# Mounting_PCB_LED.net
KiCad netlist of a schematic drawn in Altium Designer
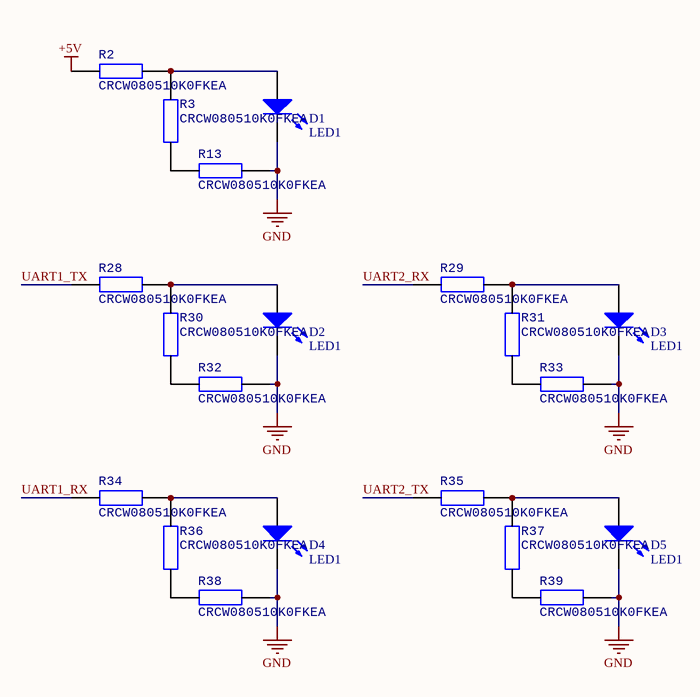
[diagram p0: Mounting_PCB_LED.SchDoc]

(export (version "E")
  (design (tool "Eeschema 10.0.6"))
  (components
    (comp (ref "D1")
      (value "LED1")
      (footprint "L0603")
      (description "Typical RED GaAs LED")
      (fields (field (name "PUBLISHER") "Altium Limited"))
      (libsource (lib "Miscellaneous Devices") (part "LED1"))
    )
    (comp (ref "D2")
      (value "LED1")
      (footprint "L0603")
      (description "Typical RED GaAs LED")
      (fields (field (name "PUBLISHER") "Altium Limited"))
      (libsource (lib "Miscellaneous Devices") (part "LED1"))
    )
    (comp (ref "D3")
      (value "LED1")
      (footprint "L0603")
      (description "Typical RED GaAs LED")
      (fields (field (name "PUBLISHER") "Altium Limited"))
      (libsource (lib "Miscellaneous Devices") (part "LED1"))
    )
    (comp (ref "D4")
      (value "LED1")
      (footprint "L0603")
      (description "Typical RED GaAs LED")
      (fields (field (name "PUBLISHER") "Altium Limited"))
      (libsource (lib "Miscellaneous Devices") (part "LED1"))
    )
    (comp (ref "D5")
      (value "LED1")
      (footprint "L0603")
      (description "Typical RED GaAs LED")
      (fields (field (name "PUBLISHER") "Altium Limited"))
      (libsource (lib "Miscellaneous Devices") (part "LED1"))
    )
    (comp (ref "R2")
      (value "CRCW080510K0FKEA")
      (footprint "RESC2012X50N")
      (fields (field (name "RS PART NUMBER") "1694499"))
      (libsource (lib "CRCW080510K0FKEA") (part "CRCW080510K0FKEA"))
    )
    (comp (ref "R3")
      (value "CRCW080510K0FKEA")
      (footprint "RESC2012X50N")
      (fields (field (name "RS PART NUMBER") "1694499"))
      (libsource (lib "CRCW080510K0FKEA") (part "CRCW080510K0FKEA"))
    )
    (comp (ref "R13")
      (value "CRCW080510K0FKEA")
      (footprint "RESC2012X50N")
      (fields (field (name "RS PART NUMBER") "1694499"))
      (libsource (lib "CRCW080510K0FKEA") (part "CRCW080510K0FKEA"))
    )
    (comp (ref "R28")
      (value "CRCW080510K0FKEA")
      (footprint "RESC2012X50N")
      (fields (field (name "RS PART NUMBER") "1694499"))
      (libsource (lib "CRCW080510K0FKEA") (part "CRCW080510K0FKEA"))
    )
    (comp (ref "R29")
      (value "CRCW080510K0FKEA")
      (footprint "RESC2012X50N")
      (fields (field (name "RS PART NUMBER") "1694499"))
      (libsource (lib "CRCW080510K0FKEA") (part "CRCW080510K0FKEA"))
    )
    (comp (ref "R30")
      (value "CRCW080510K0FKEA")
      (footprint "RESC2012X50N")
      (fields (field (name "RS PART NUMBER") "1694499"))
      (libsource (lib "CRCW080510K0FKEA") (part "CRCW080510K0FKEA"))
    )
    (comp (ref "R31")
      (value "CRCW080510K0FKEA")
      (footprint "RESC2012X50N")
      (fields (field (name "RS PART NUMBER") "1694499"))
      (libsource (lib "CRCW080510K0FKEA") (part "CRCW080510K0FKEA"))
    )
    (comp (ref "R32")
      (value "CRCW080510K0FKEA")
      (footprint "RESC2012X50N")
      (fields (field (name "RS PART NUMBER") "1694499"))
      (libsource (lib "CRCW080510K0FKEA") (part "CRCW080510K0FKEA"))
    )
    (comp (ref "R33")
      (value "CRCW080510K0FKEA")
      (footprint "RESC2012X50N")
      (fields (field (name "RS PART NUMBER") "1694499"))
      (libsource (lib "CRCW080510K0FKEA") (part "CRCW080510K0FKEA"))
    )
    (comp (ref "R34")
      (value "CRCW080510K0FKEA")
      (footprint "RESC2012X50N")
      (fields (field (name "RS PART NUMBER") "1694499"))
      (libsource (lib "CRCW080510K0FKEA") (part "CRCW080510K0FKEA"))
    )
    (comp (ref "R35")
      (value "CRCW080510K0FKEA")
      (footprint "RESC2012X50N")
      (fields (field (name "RS PART NUMBER") "1694499"))
      (libsource (lib "CRCW080510K0FKEA") (part "CRCW080510K0FKEA"))
    )
    (comp (ref "R36")
      (value "CRCW080510K0FKEA")
      (footprint "RESC2012X50N")
      (fields (field (name "RS PART NUMBER") "1694499"))
      (libsource (lib "CRCW080510K0FKEA") (part "CRCW080510K0FKEA"))
    )
    (comp (ref "R37")
      (value "CRCW080510K0FKEA")
      (footprint "RESC2012X50N")
      (fields (field (name "RS PART NUMBER") "1694499"))
      (libsource (lib "CRCW080510K0FKEA") (part "CRCW080510K0FKEA"))
    )
    (comp (ref "R38")
      (value "CRCW080510K0FKEA")
      (footprint "RESC2012X50N")
      (fields (field (name "RS PART NUMBER") "1694499"))
      (libsource (lib "CRCW080510K0FKEA") (part "CRCW080510K0FKEA"))
    )
    (comp (ref "R39")
      (value "CRCW080510K0FKEA")
      (footprint "RESC2012X50N")
      (fields (field (name "RS PART NUMBER") "1694499"))
      (libsource (lib "CRCW080510K0FKEA") (part "CRCW080510K0FKEA"))
    )
  )
  (nets
    (net (code "1") (name "+5V") (class "Default")
      (node (ref "R2") (pin "1") (pinfunction "1_1") (pintype "passive"))
    )
    (net (code "2") (name "/UART1_RX") (class "Default")
      (node (ref "R34") (pin "1") (pinfunction "1_1") (pintype "passive"))
    )
    (net (code "3") (name "/UART1_TX") (class "Default")
      (node (ref "R28") (pin "1") (pinfunction "1_1") (pintype "passive"))
    )
    (net (code "4") (name "/UART2_RX") (class "Default")
      (node (ref "R29") (pin "1") (pinfunction "1_1") (pintype "passive"))
    )
    (net (code "5") (name "/UART2_TX") (class "Default")
      (node (ref "R35") (pin "1") (pinfunction "1_1") (pintype "passive"))
    )
    (net (code "6") (name "GND") (class "Default")
      (node (ref "D1") (pin "2") (pinfunction "K_2") (pintype "passive"))
      (node (ref "D2") (pin "2") (pinfunction "K_2") (pintype "passive"))
      (node (ref "D3") (pin "2") (pinfunction "K_2") (pintype "passive"))
      (node (ref "D4") (pin "2") (pinfunction "K_2") (pintype "passive"))
      (node (ref "D5") (pin "2") (pinfunction "K_2") (pintype "passive"))
      (node (ref "R13") (pin "1") (pinfunction "1_1") (pintype "passive"))
      (node (ref "R32") (pin "1") (pinfunction "1_1") (pintype "passive"))
      (node (ref "R33") (pin "1") (pinfunction "1_1") (pintype "passive"))
      (node (ref "R38") (pin "1") (pinfunction "1_1") (pintype "passive"))
      (node (ref "R39") (pin "1") (pinfunction "1_1") (pintype "passive"))
    )
    (net (code "7") (name "Net-(D1-A)") (class "Default")
      (node (ref "D1") (pin "1") (pinfunction "A_1") (pintype "passive"))
      (node (ref "R2") (pin "2") (pinfunction "2_2") (pintype "passive"))
      (node (ref "R3") (pin "2") (pinfunction "2_2") (pintype "passive"))
    )
    (net (code "8") (name "Net-(D2-A)") (class "Default")
      (node (ref "D2") (pin "1") (pinfunction "A_1") (pintype "passive"))
      (node (ref "R28") (pin "2") (pinfunction "2_2") (pintype "passive"))
      (node (ref "R30") (pin "2") (pinfunction "2_2") (pintype "passive"))
    )
    (net (code "9") (name "Net-(D3-A)") (class "Default")
      (node (ref "D3") (pin "1") (pinfunction "A_1") (pintype "passive"))
      (node (ref "R29") (pin "2") (pinfunction "2_2") (pintype "passive"))
      (node (ref "R31") (pin "2") (pinfunction "2_2") (pintype "passive"))
    )
    (net (code "10") (name "Net-(D4-A)") (class "Default")
      (node (ref "D4") (pin "1") (pinfunction "A_1") (pintype "passive"))
      (node (ref "R34") (pin "2") (pinfunction "2_2") (pintype "passive"))
      (node (ref "R36") (pin "2") (pinfunction "2_2") (pintype "passive"))
    )
    (net (code "11") (name "Net-(D5-A)") (class "Default")
      (node (ref "D5") (pin "1") (pinfunction "A_1") (pintype "passive"))
      (node (ref "R35") (pin "2") (pinfunction "2_2") (pintype "passive"))
      (node (ref "R37") (pin "2") (pinfunction "2_2") (pintype "passive"))
    )
    (net (code "12") (name "Net-(R13-Pad2)") (class "Default")
      (node (ref "R13") (pin "2") (pinfunction "2_2") (pintype "passive"))
      (node (ref "R3") (pin "1") (pinfunction "1_1") (pintype "passive"))
    )
    (net (code "13") (name "Net-(R30-Pad1)") (class "Default")
      (node (ref "R30") (pin "1") (pinfunction "1_1") (pintype "passive"))
      (node (ref "R32") (pin "2") (pinfunction "2_2") (pintype "passive"))
    )
    (net (code "14") (name "Net-(R31-Pad1)") (class "Default")
      (node (ref "R31") (pin "1") (pinfunction "1_1") (pintype "passive"))
      (node (ref "R33") (pin "2") (pinfunction "2_2") (pintype "passive"))
    )
    (net (code "15") (name "Net-(R36-Pad1)") (class "Default")
      (node (ref "R36") (pin "1") (pinfunction "1_1") (pintype "passive"))
      (node (ref "R38") (pin "2") (pinfunction "2_2") (pintype "passive"))
    )
    (net (code "16") (name "Net-(R37-Pad1)") (class "Default")
      (node (ref "R37") (pin "1") (pinfunction "1_1") (pintype "passive"))
      (node (ref "R39") (pin "2") (pinfunction "2_2") (pintype "passive"))
    )
  )
)
